# module.net
KiCad netlist of a schematic drawn in Altium Designer
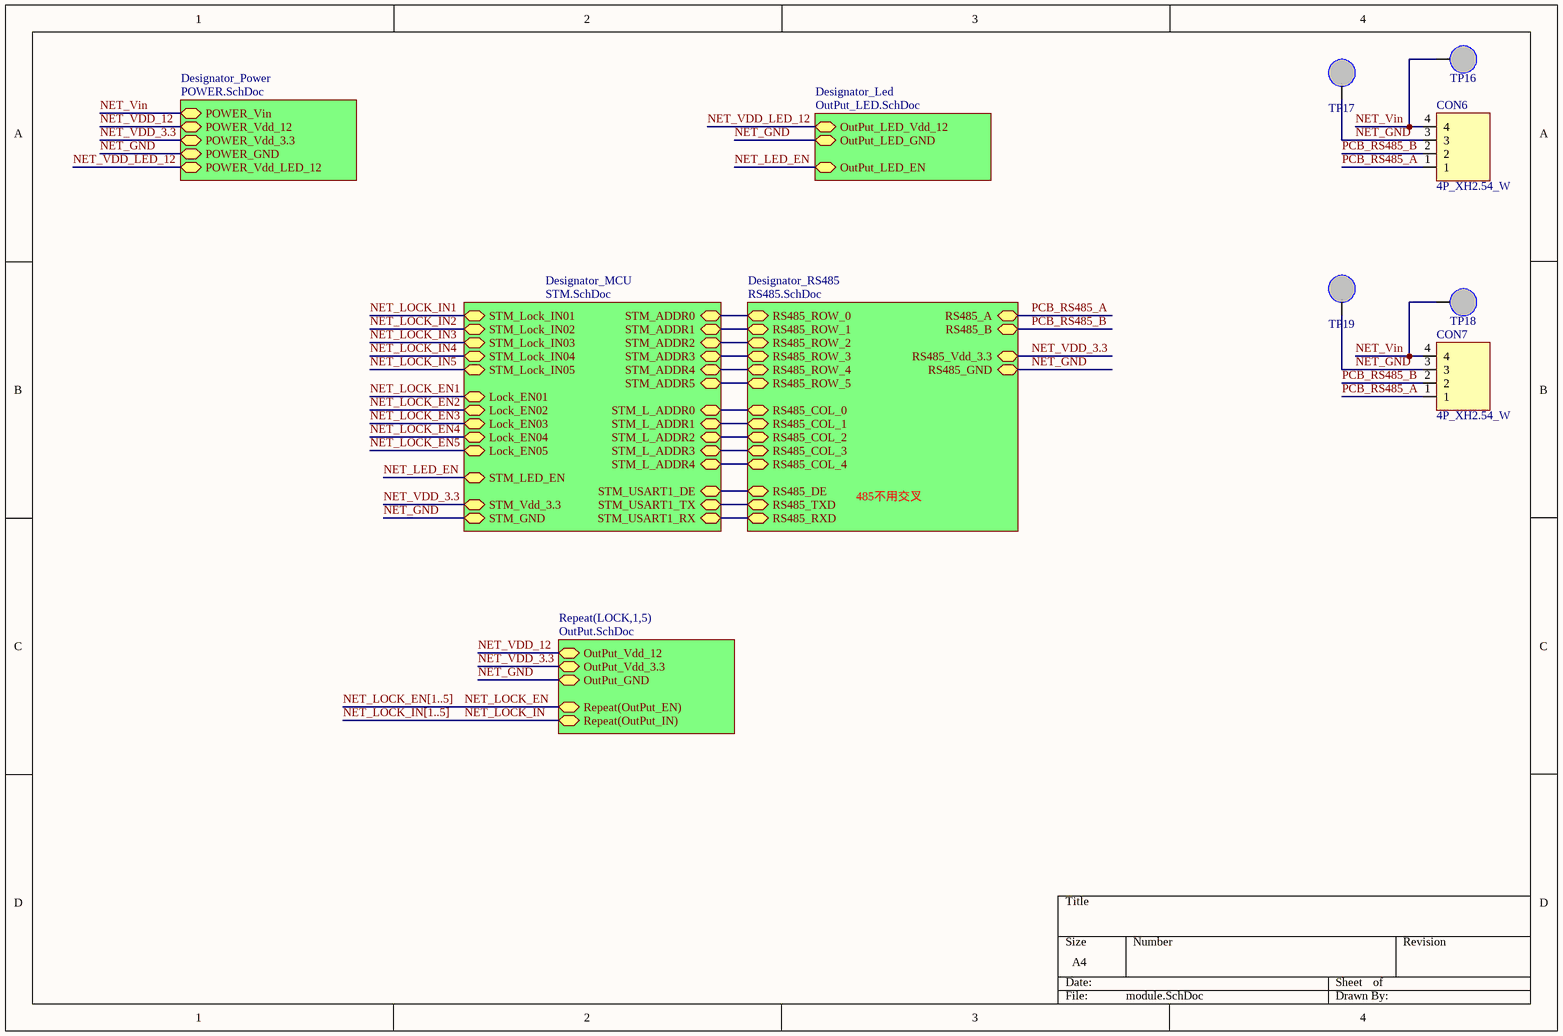
[diagram p0: module.SchDoc]

(export (version "E")
  (design (tool "Eeschema 10.0.6"))
  (components
    (comp (ref "CON6")
      (value "4P_XH2.54_W")
      (footprint "XH2.54-WS-4P")
      (libsource (lib "mylib") (part "4P_XH2.54_W"))
    )
    (comp (ref "CON7")
      (value "4P_XH2.54_W")
      (footprint "XH2.54-WS-4P")
      (libsource (lib "mylib") (part "4P_XH2.54_W"))
    )
    (comp (ref "TP16") (value "TP") (footprint "TP") (libsource (lib "mylib") (part "TP")))
    (comp (ref "TP17") (value "TP") (footprint "TP") (libsource (lib "mylib") (part "TP")))
    (comp (ref "TP18") (value "TP") (footprint "TP") (libsource (lib "mylib") (part "TP")))
    (comp (ref "TP19") (value "TP") (footprint "TP") (libsource (lib "mylib") (part "TP")))
  )
  (nets
    (net (code "1") (name "/NET_GND") (class "Default")
      (node (ref "CON6") (pin "3") (pinfunction "3_3") (pintype "passive"))
      (node (ref "CON7") (pin "3") (pinfunction "3_3") (pintype "passive"))
      (node (ref "TP17") (pin "1") (pinfunction "1_1") (pintype "passive"))
      (node (ref "TP19") (pin "1") (pinfunction "1_1") (pintype "passive"))
    )
    (net (code "20") (name "/NET_Vin") (class "Default")
      (node (ref "CON6") (pin "4") (pinfunction "4_4") (pintype "passive"))
      (node (ref "CON7") (pin "4") (pinfunction "4_4") (pintype "passive"))
      (node (ref "TP16") (pin "1") (pinfunction "1_1") (pintype "passive"))
      (node (ref "TP18") (pin "1") (pinfunction "1_1") (pintype "passive"))
    )
    (net (code "21") (name "/PCB_RS485_A") (class "Default")
      (node (ref "CON6") (pin "1") (pinfunction "1_1") (pintype "passive"))
      (node (ref "CON7") (pin "1") (pinfunction "1_1") (pintype "passive"))
    )
    (net (code "22") (name "/PCB_RS485_B") (class "Default")
      (node (ref "CON6") (pin "2") (pinfunction "2_2") (pintype "passive"))
      (node (ref "CON7") (pin "2") (pinfunction "2_2") (pintype "passive"))
    )
    (net (code "37") (name "unconnected-(CON6-PadA)") (class "Default")
      (node (ref "CON6") (pin "A") (pinfunction "A_A") (pintype "passive"))
    )
    (net (code "38") (name "unconnected-(CON6-PadB)") (class "Default")
      (node (ref "CON6") (pin "B") (pinfunction "B_B") (pintype "passive"))
    )
    (net (code "39") (name "unconnected-(CON7-PadA)") (class "Default")
      (node (ref "CON7") (pin "A") (pinfunction "A_A") (pintype "passive"))
    )
    (net (code "40") (name "unconnected-(CON7-PadB)") (class "Default")
      (node (ref "CON7") (pin "B") (pinfunction "B_B") (pintype "passive"))
    )
  )
)
